# WiFi.net
KiCad netlist of a schematic drawn in Altium Designer
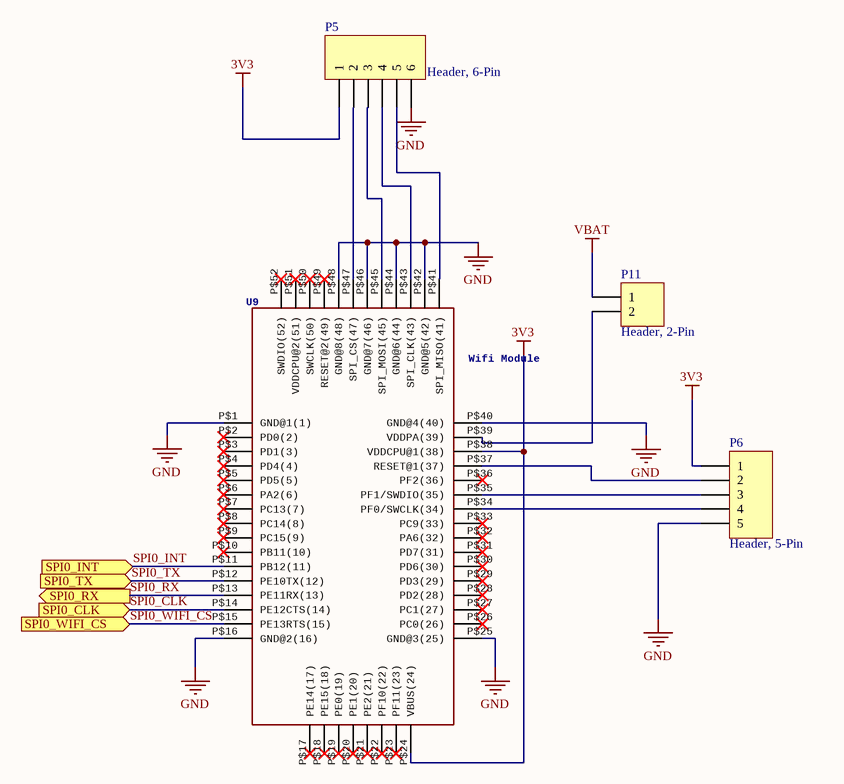
[diagram p0: WiFi.SchDoc]

(export (version "E")
  (design (tool "Eeschema 10.0.6"))
  (components
    (comp (ref "P5")
      (value "Header, 6-Pin")
      (footprint "HDR1X6")
      (fields (field (name "PUBLISHER") "Altium Limited"))
      (libsource (lib "Miscellaneous Connectors") (part "Header 6"))
    )
    (comp (ref "P6")
      (value "Header, 5-Pin")
      (footprint "HDR1X5")
      (fields (field (name "PUBLISHER") "Altium Limited"))
      (libsource (lib "Miscellaneous Connectors") (part "Header 5"))
    )
    (comp (ref "P11")
      (value "Header, 2-Pin")
      (footprint "HDR1X2")
      (fields (field (name "PUBLISHER") "Altium Limited"))
      (libsource (lib "Miscellaneous Connectors") (part "Header 2"))
    )
    (comp (ref "U9")
      (value "Wifi Module")
      (footprint "WGM110_PAC")
      (libsource (lib "LowPower_3ER_Parts") (part "WGM110_DEV"))
    )
  )
  (nets
    (net (code "1") (name "/SPI0_CLK") (class "Default")
      (node (ref "U9") (pin "P$14") (pinfunction "PE12CTS(14)_P$14") (pintype "passive"))
    )
    (net (code "2") (name "/SPI0_INT") (class "Default")
      (node (ref "U9") (pin "P$11") (pinfunction "PB12(11)_P$11") (pintype "passive"))
    )
    (net (code "3") (name "/SPI0_RX") (class "Default")
      (node (ref "U9") (pin "P$13") (pinfunction "PE11RX(13)_P$13") (pintype "passive"))
    )
    (net (code "4") (name "/SPI0_TX") (class "Default")
      (node (ref "U9") (pin "P$12") (pinfunction "PE10TX(12)_P$12") (pintype "passive"))
    )
    (net (code "5") (name "/SPI0_WIFI_CS") (class "Default")
      (node (ref "U9") (pin "P$15") (pinfunction "PE13RTS(15)_P$15") (pintype "passive"))
    )
    (net (code "6") (name "3V3") (class "Default")
      (node (ref "P5") (pin "1") (pinfunction "1_1") (pintype "passive"))
      (node (ref "P6") (pin "1") (pinfunction "1_1") (pintype "passive"))
      (node (ref "U9") (pin "P$24") (pinfunction "VBUS(24)_P$24") (pintype "power_in"))
      (node (ref "U9") (pin "P$38") (pinfunction "VDDCPU@1(38)_P$38") (pintype "power_in"))
    )
    (net (code "7") (name "GND") (class "Default")
      (node (ref "P5") (pin "6") (pinfunction "6_6") (pintype "passive"))
      (node (ref "P6") (pin "5") (pinfunction "5_5") (pintype "passive"))
      (node (ref "U9") (pin "P$1") (pinfunction "GND@1(1)_P$1") (pintype "power_in"))
      (node (ref "U9") (pin "P$16") (pinfunction "GND@2(16)_P$16") (pintype "power_in"))
      (node (ref "U9") (pin "P$25") (pinfunction "GND@3(25)_P$25") (pintype "power_in"))
      (node (ref "U9") (pin "P$40") (pinfunction "GND@4(40)_P$40") (pintype "power_in"))
      (node (ref "U9") (pin "P$42") (pinfunction "GND@5(42)_P$42") (pintype "power_in"))
      (node (ref "U9") (pin "P$44") (pinfunction "GND@6(44)_P$44") (pintype "power_in"))
      (node (ref "U9") (pin "P$46") (pinfunction "GND@7(46)_P$46") (pintype "power_in"))
      (node (ref "U9") (pin "P$48") (pinfunction "GND@8(48)_P$48") (pintype "power_in"))
    )
    (net (code "8") (name "Net-(U9-PF0{slash}SWCLK(34))") (class "Default")
      (node (ref "P6") (pin "4") (pinfunction "4_4") (pintype "passive"))
      (node (ref "U9") (pin "P$34") (pinfunction "PF0/SWCLK(34)_P$34") (pintype "passive"))
    )
    (net (code "9") (name "Net-(U9-PF1{slash}SWDIO(35))") (class "Default")
      (node (ref "P6") (pin "3") (pinfunction "3_3") (pintype "passive"))
      (node (ref "U9") (pin "P$35") (pinfunction "PF1/SWDIO(35)_P$35") (pintype "passive"))
    )
    (net (code "10") (name "Net-(U9-RESET@1(37))") (class "Default")
      (node (ref "P6") (pin "2") (pinfunction "2_2") (pintype "passive"))
      (node (ref "U9") (pin "P$37") (pinfunction "RESET@1(37)_P$37") (pintype "passive"))
    )
    (net (code "11") (name "Net-(U9-SPI_CLK(43))") (class "Default")
      (node (ref "P5") (pin "4") (pinfunction "4_4") (pintype "passive"))
      (node (ref "U9") (pin "P$43") (pinfunction "SPI_CLK(43)_P$43") (pintype "passive"))
    )
    (net (code "12") (name "Net-(U9-SPI_CS(47))") (class "Default")
      (node (ref "P5") (pin "2") (pinfunction "2_2") (pintype "passive"))
      (node (ref "U9") (pin "P$47") (pinfunction "SPI_CS(47)_P$47") (pintype "passive"))
    )
    (net (code "13") (name "Net-(U9-SPI_MISO(41))") (class "Default")
      (node (ref "P5") (pin "5") (pinfunction "5_5") (pintype "passive"))
      (node (ref "U9") (pin "P$41") (pinfunction "SPI_MISO(41)_P$41") (pintype "passive"))
    )
    (net (code "14") (name "Net-(U9-SPI_MOSI(45))") (class "Default")
      (node (ref "P5") (pin "3") (pinfunction "3_3") (pintype "passive"))
      (node (ref "U9") (pin "P$45") (pinfunction "SPI_MOSI(45)_P$45") (pintype "passive"))
    )
    (net (code "15") (name "Net-(U9-VDDPA(39))") (class "Default")
      (node (ref "P11") (pin "2") (pinfunction "2_2") (pintype "passive"))
      (node (ref "U9") (pin "P$39") (pinfunction "VDDPA(39)_P$39") (pintype "power_in"))
    )
    (net (code "16") (name "VBAT") (class "Default")
      (node (ref "P11") (pin "1") (pinfunction "1_1") (pintype "passive"))
    )
    (net (code "17") (name "unconnected-(U9-PA2(6)-PadP$6)") (class "Default")
      (node (ref "U9") (pin "P$6") (pinfunction "PA2(6)_P$6") (pintype "passive+no_connect"))
    )
    (net (code "18") (name "unconnected-(U9-PA6(32)-PadP$32)") (class "Default")
      (node (ref "U9") (pin "P$32") (pinfunction "PA6(32)_P$32") (pintype "passive+no_connect"))
    )
    (net (code "19") (name "unconnected-(U9-PB11(10)-PadP$10)") (class "Default")
      (node (ref "U9") (pin "P$10") (pinfunction "PB11(10)_P$10") (pintype "passive+no_connect"))
    )
    (net (code "20") (name "unconnected-(U9-PC0(26)-PadP$26)") (class "Default")
      (node (ref "U9") (pin "P$26") (pinfunction "PC0(26)_P$26") (pintype "passive+no_connect"))
    )
    (net (code "21") (name "unconnected-(U9-PC1(27)-PadP$27)") (class "Default")
      (node (ref "U9") (pin "P$27") (pinfunction "PC1(27)_P$27") (pintype "passive+no_connect"))
    )
    (net (code "22") (name "unconnected-(U9-PC9(33)-PadP$33)") (class "Default")
      (node (ref "U9") (pin "P$33") (pinfunction "PC9(33)_P$33") (pintype "passive+no_connect"))
    )
    (net (code "23") (name "unconnected-(U9-PC13(7)-PadP$7)") (class "Default")
      (node (ref "U9") (pin "P$7") (pinfunction "PC13(7)_P$7") (pintype "passive+no_connect"))
    )
    (net (code "24") (name "unconnected-(U9-PC14(8)-PadP$8)") (class "Default")
      (node (ref "U9") (pin "P$8") (pinfunction "PC14(8)_P$8") (pintype "passive+no_connect"))
    )
    (net (code "25") (name "unconnected-(U9-PC15(9)-PadP$9)") (class "Default")
      (node (ref "U9") (pin "P$9") (pinfunction "PC15(9)_P$9") (pintype "passive+no_connect"))
    )
    (net (code "26") (name "unconnected-(U9-PD0(2)-PadP$2)") (class "Default")
      (node (ref "U9") (pin "P$2") (pinfunction "PD0(2)_P$2") (pintype "passive+no_connect"))
    )
    (net (code "27") (name "unconnected-(U9-PD1(3)-PadP$3)") (class "Default")
      (node (ref "U9") (pin "P$3") (pinfunction "PD1(3)_P$3") (pintype "passive+no_connect"))
    )
    (net (code "28") (name "unconnected-(U9-PD2(28)-PadP$28)") (class "Default")
      (node (ref "U9") (pin "P$28") (pinfunction "PD2(28)_P$28") (pintype "passive+no_connect"))
    )
    (net (code "29") (name "unconnected-(U9-PD3(29)-PadP$29)") (class "Default")
      (node (ref "U9") (pin "P$29") (pinfunction "PD3(29)_P$29") (pintype "passive+no_connect"))
    )
    (net (code "30") (name "unconnected-(U9-PD4(4)-PadP$4)") (class "Default")
      (node (ref "U9") (pin "P$4") (pinfunction "PD4(4)_P$4") (pintype "passive+no_connect"))
    )
    (net (code "31") (name "unconnected-(U9-PD5(5)-PadP$5)") (class "Default")
      (node (ref "U9") (pin "P$5") (pinfunction "PD5(5)_P$5") (pintype "passive+no_connect"))
    )
    (net (code "32") (name "unconnected-(U9-PD6(30)-PadP$30)") (class "Default")
      (node (ref "U9") (pin "P$30") (pinfunction "PD6(30)_P$30") (pintype "passive+no_connect"))
    )
    (net (code "33") (name "unconnected-(U9-PD7(31)-PadP$31)") (class "Default")
      (node (ref "U9") (pin "P$31") (pinfunction "PD7(31)_P$31") (pintype "passive+no_connect"))
    )
    (net (code "34") (name "unconnected-(U9-PE0(19)-PadP$19)") (class "Default")
      (node (ref "U9") (pin "P$19") (pinfunction "PE0(19)_P$19") (pintype "passive+no_connect"))
    )
    (net (code "35") (name "unconnected-(U9-PE1(20)-PadP$20)") (class "Default")
      (node (ref "U9") (pin "P$20") (pinfunction "PE1(20)_P$20") (pintype "passive+no_connect"))
    )
    (net (code "36") (name "unconnected-(U9-PE2(21)-PadP$21)") (class "Default")
      (node (ref "U9") (pin "P$21") (pinfunction "PE2(21)_P$21") (pintype "passive+no_connect"))
    )
    (net (code "37") (name "unconnected-(U9-PE14(17)-PadP$17)") (class "Default")
      (node (ref "U9") (pin "P$17") (pinfunction "PE14(17)_P$17") (pintype "passive+no_connect"))
    )
    (net (code "38") (name "unconnected-(U9-PE15(18)-PadP$18)") (class "Default")
      (node (ref "U9") (pin "P$18") (pinfunction "PE15(18)_P$18") (pintype "passive+no_connect"))
    )
    (net (code "39") (name "unconnected-(U9-PF2(36)-PadP$36)") (class "Default")
      (node (ref "U9") (pin "P$36") (pinfunction "PF2(36)_P$36") (pintype "passive+no_connect"))
    )
    (net (code "40") (name "unconnected-(U9-PF10(22)-PadP$22)") (class "Default")
      (node (ref "U9") (pin "P$22") (pinfunction "PF10(22)_P$22") (pintype "passive+no_connect"))
    )
    (net (code "41") (name "unconnected-(U9-PF11(23)-PadP$23)") (class "Default")
      (node (ref "U9") (pin "P$23") (pinfunction "PF11(23)_P$23") (pintype "passive+no_connect"))
    )
    (net (code "42") (name "unconnected-(U9-RESET@2(49)-PadP$49)") (class "Default")
      (node (ref "U9") (pin "P$49") (pinfunction "RESET@2(49)_P$49") (pintype "passive+no_connect"))
    )
    (net (code "43") (name "unconnected-(U9-SWCLK(50)-PadP$50)") (class "Default")
      (node (ref "U9") (pin "P$50") (pinfunction "SWCLK(50)_P$50") (pintype "passive+no_connect"))
    )
    (net (code "44") (name "unconnected-(U9-SWDIO(52)-PadP$52)") (class "Default")
      (node (ref "U9") (pin "P$52") (pinfunction "SWDIO(52)_P$52") (pintype "passive+no_connect"))
    )
    (net (code "45") (name "unconnected-(U9-VDDCPU@2(51)-PadP$51)") (class "Default")
      (node (ref "U9") (pin "P$51") (pinfunction "VDDCPU@2(51)_P$51") (pintype "power_in+no_connect"))
    )
  )
)
